# SCH_NFC-Llamacard_2024-08-04.net
KiCad netlist of a schematic drawn in EasyEDA
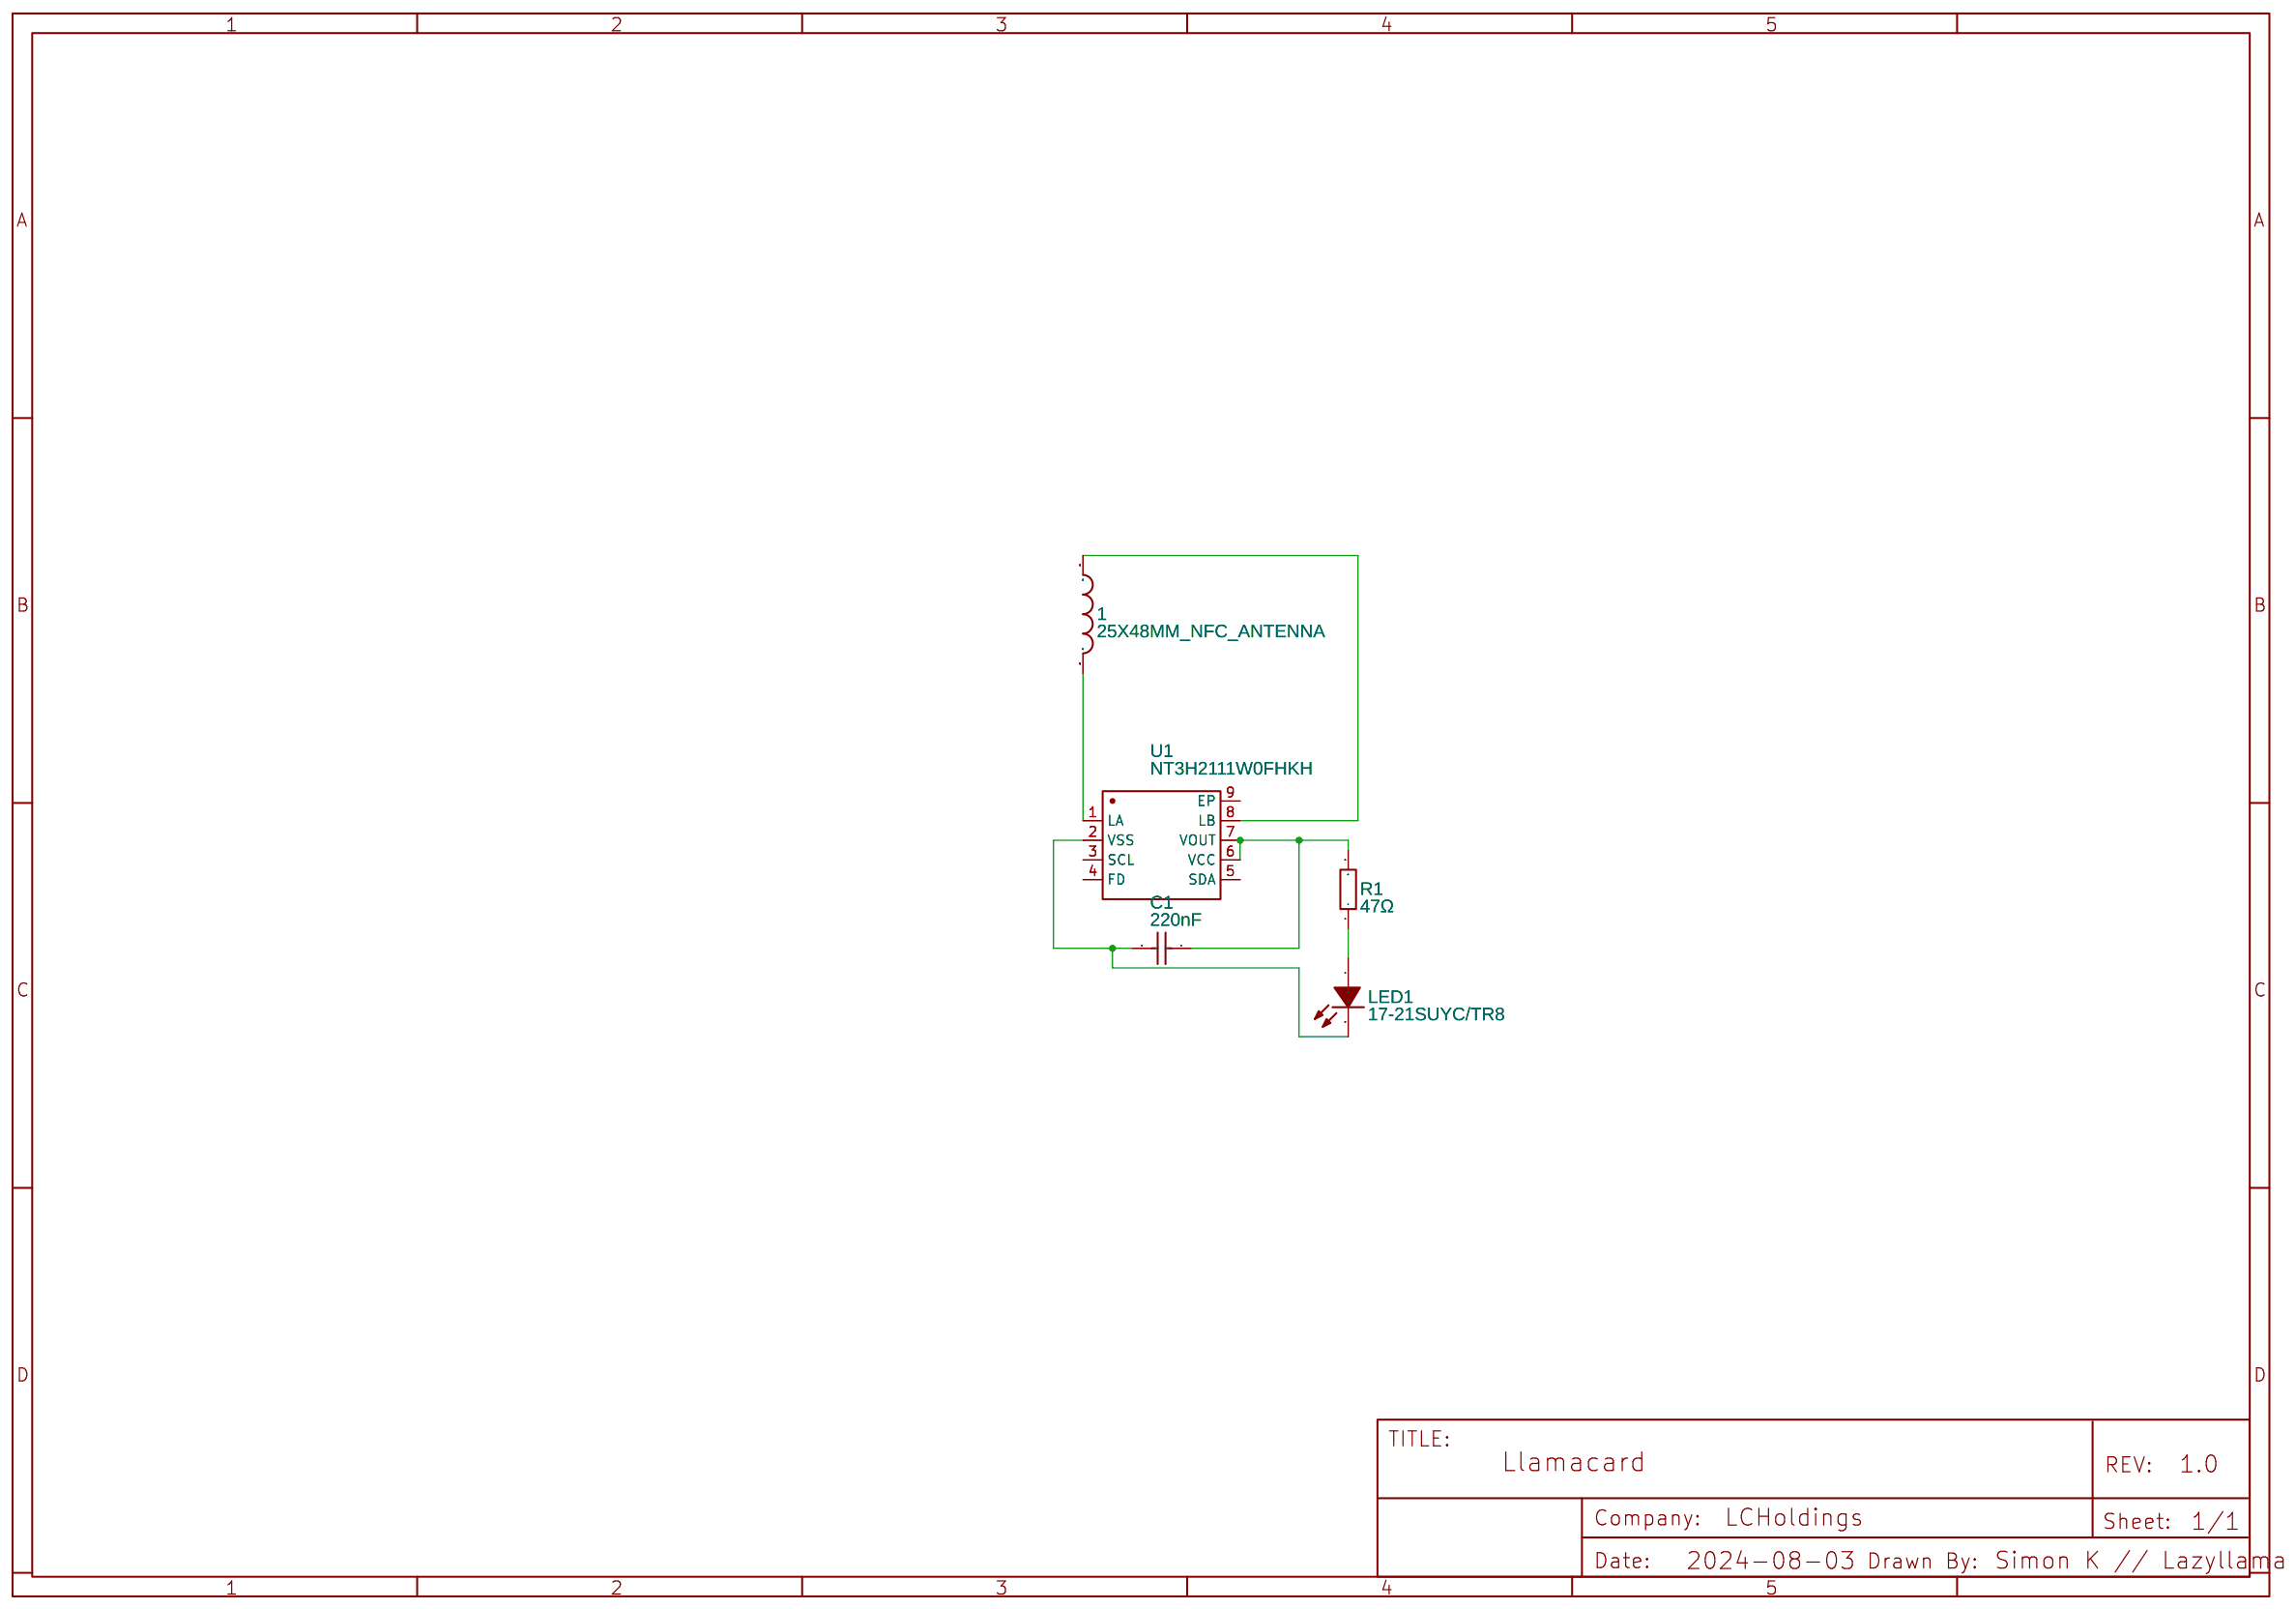
[diagram p0: schematic sheet]

(export (version "E")
  (design (tool "Eeschema 10.0.6"))
  (components
    (comp (ref "1") (value "25X48MM_NFC_ANTENNA") (libsource (lib "") (part "25X48MM_NFC_ANTENNA")))
    (comp (ref "C1")
      (value "220nF")
      (fields
        (field (name "Manufacturer Part") "CL10B224KA8NNNC")
        (field (name "Manufacturer") "SAMSUNG(三星)")
      )
      (libsource (lib "") (part "CL10B224KA8NNNC"))
    )
    (comp (ref "LED1")
      (value "17-21SUYC/TR8")
      (fields (field (name "Manufacturer Part") "KT-0805黄灯") (field (name "Manufacturer") "KENTO"))
      (libsource (lib "") (part "17-21SUYC/TR8"))
    )
    (comp (ref "R1")
      (value "47Ω")
      (fields
        (field (name "Manufacturer Part") "0603WAF470JT5E")
        (field (name "Manufacturer") "UNI-ROYAL(厚声)")
      )
      (libsource (lib "") (part "0603WAF470JT5E"))
    )
    (comp (ref "U1")
      (value "NT3H2111W0FHKH")
      (fields (field (name "Manufacturer") "NXP(恩智浦)"))
      (libsource (lib "") (part "NT3H2111W0FHKH"))
    )
  )
  (nets
    (net (code "1") (name "Net-(LED1-+)") (class "Default")
      (node (ref "LED1") (pin "1") (pinfunction "+_1") (pintype "unspecified"))
      (node (ref "R1") (pin "1") (pinfunction "1_1") (pintype "input"))
    )
    (net (code "2") (name "Net-(LED1--)") (class "Default")
      (node (ref "C1") (pin "2") (pinfunction "2_2") (pintype "input"))
      (node (ref "LED1") (pin "2") (pinfunction "-_2") (pintype "unspecified"))
      (node (ref "U1") (pin "2") (pinfunction "VSS_2") (pintype "unspecified"))
    )
    (net (code "3") (name "Net-(U1-LA)") (class "Default")
      (node (ref "1") (pin "P$2") (pinfunction "P$2_P$2") (pintype "bidirectional"))
      (node (ref "U1") (pin "1") (pinfunction "LA_1") (pintype "unspecified"))
    )
    (net (code "4") (name "Net-(U1-LB)") (class "Default")
      (node (ref "1") (pin "P$1") (pinfunction "P$1_P$1") (pintype "bidirectional"))
      (node (ref "U1") (pin "8") (pinfunction "LB_8") (pintype "unspecified"))
    )
    (net (code "5") (name "Net-(U1-VCC)") (class "Default")
      (node (ref "C1") (pin "1") (pinfunction "1_1") (pintype "input"))
      (node (ref "R1") (pin "2") (pinfunction "2_2") (pintype "input"))
      (node (ref "U1") (pin "6") (pinfunction "VCC_6") (pintype "unspecified"))
      (node (ref "U1") (pin "7") (pinfunction "VOUT_7") (pintype "unspecified"))
    )
    (net (code "6") (name "unconnected-(U1-EP-Pad9)") (class "Default")
      (node (ref "U1") (pin "9") (pinfunction "EP_9") (pintype "unspecified"))
    )
    (net (code "7") (name "unconnected-(U1-FD-Pad4)") (class "Default")
      (node (ref "U1") (pin "4") (pinfunction "FD_4") (pintype "unspecified"))
    )
    (net (code "8") (name "unconnected-(U1-SCL-Pad3)") (class "Default")
      (node (ref "U1") (pin "3") (pinfunction "SCL_3") (pintype "unspecified"))
    )
    (net (code "9") (name "unconnected-(U1-SDA-Pad5)") (class "Default")
      (node (ref "U1") (pin "5") (pinfunction "SDA_5") (pintype "unspecified"))
    )
  )
)
